# DE100-hw.net
KiCad netlist of a schematic drawn in EAGLE
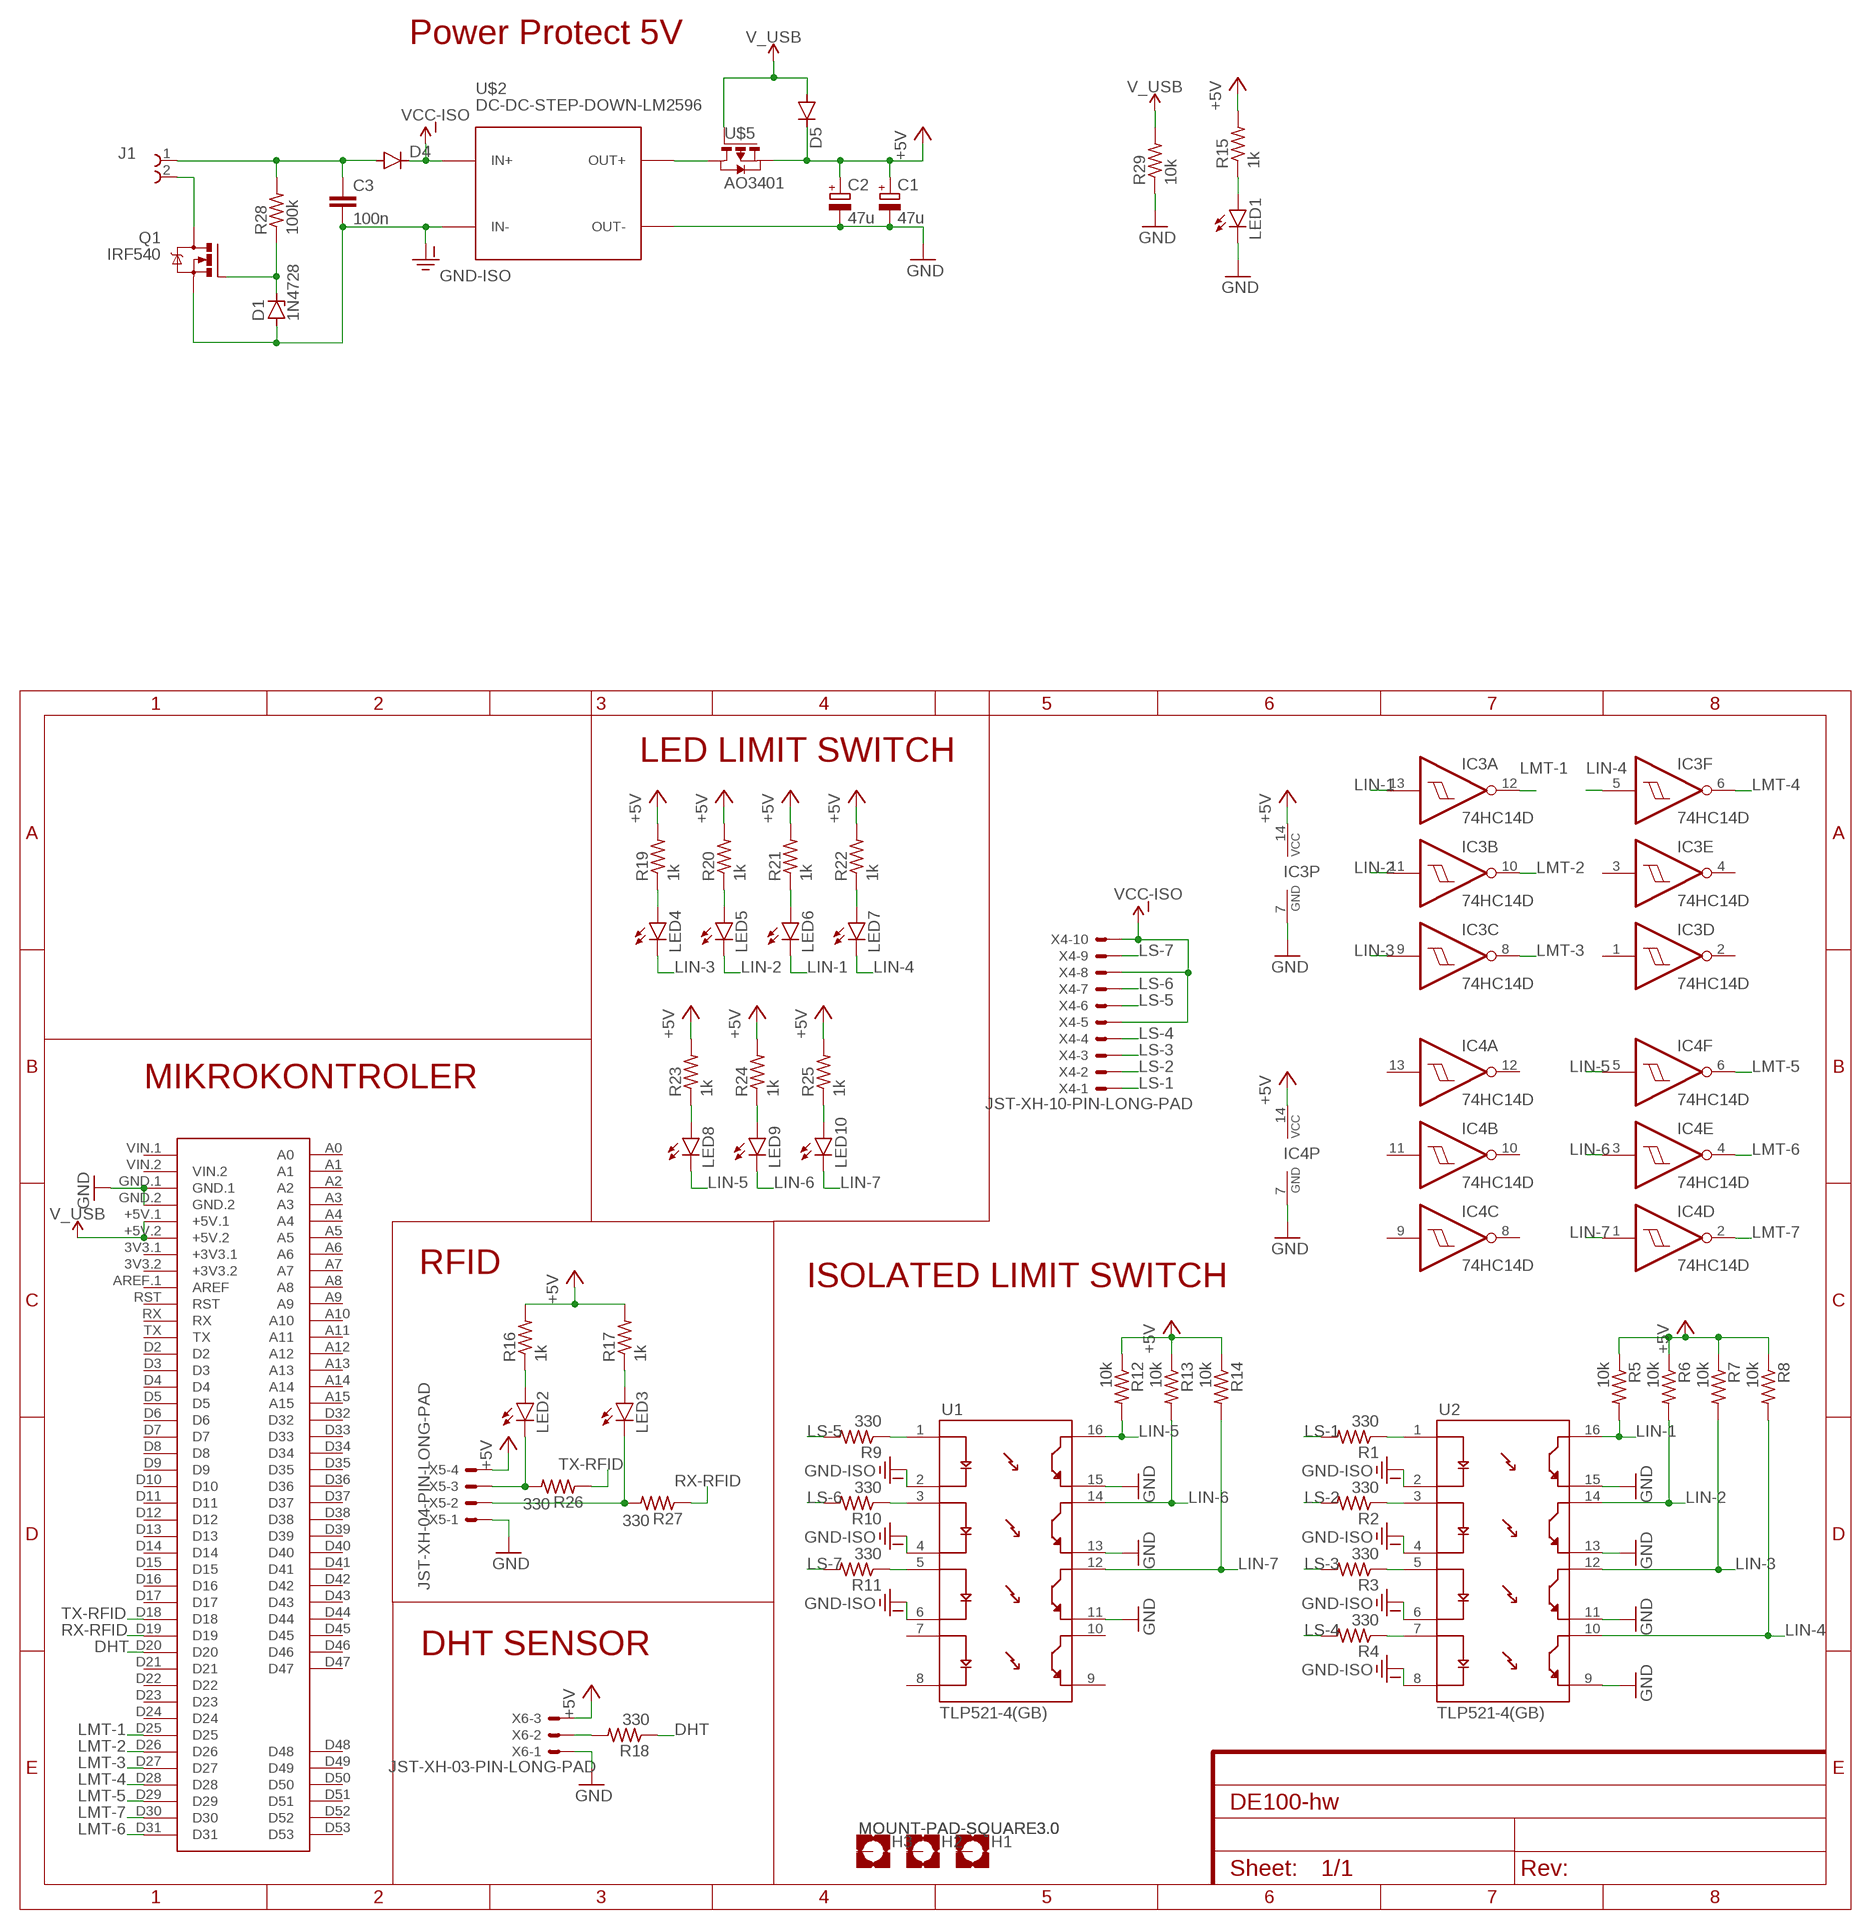
[diagram p0: schematic, sheet 1]

(export (version "E")
  (design (tool "Eeschema 10.0.6"))
  (components
    (comp (ref "C1")
      (value "47u")
      (footprint "eagle-import:UD-6,3X5,8_NICHICON")
      (libsource (lib "eagle-import") (part "CPOL-EUUD-6,3X8,8"))
    )
    (comp (ref "C2")
      (value "47u")
      (footprint "eagle-import:UD-6,3X5,8_NICHICON")
      (libsource (lib "eagle-import") (part "CPOL-EUUD-6,3X8,8"))
    )
    (comp (ref "C3")
      (value "100n")
      (footprint "eagle-import:C0805K")
      (libsource (lib "eagle-import") (part "C-EUC0805K"))
    )
    (comp (ref "D1")
      (value "1N4728")
      (footprint "eagle-import:DO41Z10")
      (libsource (lib "eagle-import") (part "1N4728"))
    )
    (comp (ref "D4")
      (value "DIODE-DO-214AC")
      (footprint "eagle-import:DO-214AC")
      (libsource (lib "eagle-import") (part "DIODE-DO-214AC"))
    )
    (comp (ref "D5")
      (value "DIODE-DO-214AC")
      (footprint "eagle-import:DO-214AC")
      (libsource (lib "eagle-import") (part "DIODE-DO-214AC"))
    )
    (comp (ref "H1")
      (value "MOUNT-PAD-SQUARE3.0")
      (footprint "eagle-import:3,0-PAD-SQUARE")
      (libsource (lib "eagle-import") (part "MOUNT-PAD-SQUARE3.0"))
    )
    (comp (ref "H2")
      (value "MOUNT-PAD-SQUARE3.0")
      (footprint "eagle-import:3,0-PAD-SQUARE")
      (libsource (lib "eagle-import") (part "MOUNT-PAD-SQUARE3.0"))
    )
    (comp (ref "H3")
      (value "MOUNT-PAD-SQUARE3.0")
      (footprint "eagle-import:3,0-PAD-SQUARE")
      (libsource (lib "eagle-import") (part "MOUNT-PAD-SQUARE3.0"))
    )
    (comp (ref "IC3")
      (value "74HC14D")
      (footprint "eagle-import:SO14")
      (libsource (lib "eagle-import") (part "7414DHC"))
    )
    (comp (ref "IC4")
      (value "74HC14D")
      (footprint "eagle-import:SO14")
      (libsource (lib "eagle-import") (part "7414DHC"))
    )
    (comp (ref "J1")
      (value "691312510002")
      (footprint "eagle-import:691312510002")
      (libsource (lib "eagle-import") (part "691312510002"))
    )
    (comp (ref "LED1")
      (value "LEDCHIPLED_0805")
      (footprint "eagle-import:CHIPLED_0805")
      (libsource (lib "eagle-import") (part "LEDCHIPLED_0805"))
    )
    (comp (ref "LED2")
      (value "LEDCHIPLED_0805")
      (footprint "eagle-import:CHIPLED_0805")
      (libsource (lib "eagle-import") (part "LEDCHIPLED_0805"))
    )
    (comp (ref "LED3")
      (value "LEDCHIPLED_0805")
      (footprint "eagle-import:CHIPLED_0805")
      (libsource (lib "eagle-import") (part "LEDCHIPLED_0805"))
    )
    (comp (ref "LED4")
      (value "LEDCHIPLED_0805")
      (footprint "eagle-import:CHIPLED_0805")
      (libsource (lib "eagle-import") (part "LEDCHIPLED_0805"))
    )
    (comp (ref "LED5")
      (value "LEDCHIPLED_0805")
      (footprint "eagle-import:CHIPLED_0805")
      (libsource (lib "eagle-import") (part "LEDCHIPLED_0805"))
    )
    (comp (ref "LED6")
      (value "LEDCHIPLED_0805")
      (footprint "eagle-import:CHIPLED_0805")
      (libsource (lib "eagle-import") (part "LEDCHIPLED_0805"))
    )
    (comp (ref "LED7")
      (value "LEDCHIPLED_0805")
      (footprint "eagle-import:CHIPLED_0805")
      (libsource (lib "eagle-import") (part "LEDCHIPLED_0805"))
    )
    (comp (ref "LED8")
      (value "LEDCHIPLED_0805")
      (footprint "eagle-import:CHIPLED_0805")
      (libsource (lib "eagle-import") (part "LEDCHIPLED_0805"))
    )
    (comp (ref "LED9")
      (value "LEDCHIPLED_0805")
      (footprint "eagle-import:CHIPLED_0805")
      (libsource (lib "eagle-import") (part "LEDCHIPLED_0805"))
    )
    (comp (ref "LED10")
      (value "LEDCHIPLED_0805")
      (footprint "eagle-import:CHIPLED_0805")
      (libsource (lib "eagle-import") (part "LEDCHIPLED_0805"))
    )
    (comp (ref "Q1")
      (value "IRF540")
      (footprint "eagle-import:TO220BV")
      (libsource (lib "eagle-import") (part "IRF540"))
    )
    (comp (ref "R1")
      (value "330")
      (footprint "eagle-import:R0805")
      (libsource (lib "eagle-import") (part "R-US_R0805"))
    )
    (comp (ref "R2")
      (value "330")
      (footprint "eagle-import:R0805")
      (libsource (lib "eagle-import") (part "R-US_R0805"))
    )
    (comp (ref "R3")
      (value "330")
      (footprint "eagle-import:R0805")
      (libsource (lib "eagle-import") (part "R-US_R0805"))
    )
    (comp (ref "R4")
      (value "330")
      (footprint "eagle-import:R0805")
      (libsource (lib "eagle-import") (part "R-US_R0805"))
    )
    (comp (ref "R5")
      (value "10k")
      (footprint "eagle-import:R0805")
      (libsource (lib "eagle-import") (part "R-US_R0805"))
    )
    (comp (ref "R6")
      (value "10k")
      (footprint "eagle-import:R0805")
      (libsource (lib "eagle-import") (part "R-US_R0805"))
    )
    (comp (ref "R7")
      (value "10k")
      (footprint "eagle-import:R0805")
      (libsource (lib "eagle-import") (part "R-US_R0805"))
    )
    (comp (ref "R8")
      (value "10k")
      (footprint "eagle-import:R0805")
      (libsource (lib "eagle-import") (part "R-US_R0805"))
    )
    (comp (ref "R9")
      (value "330")
      (footprint "eagle-import:R0805")
      (libsource (lib "eagle-import") (part "R-US_R0805"))
    )
    (comp (ref "R10")
      (value "330")
      (footprint "eagle-import:R0805")
      (libsource (lib "eagle-import") (part "R-US_R0805"))
    )
    (comp (ref "R11")
      (value "330")
      (footprint "eagle-import:R0805")
      (libsource (lib "eagle-import") (part "R-US_R0805"))
    )
    (comp (ref "R12")
      (value "10k")
      (footprint "eagle-import:R0805")
      (libsource (lib "eagle-import") (part "R-US_R0805"))
    )
    (comp (ref "R13")
      (value "10k")
      (footprint "eagle-import:R0805")
      (libsource (lib "eagle-import") (part "R-US_R0805"))
    )
    (comp (ref "R14")
      (value "10k")
      (footprint "eagle-import:R0805")
      (libsource (lib "eagle-import") (part "R-US_R0805"))
    )
    (comp (ref "R15")
      (value "1k")
      (footprint "eagle-import:R0805")
      (libsource (lib "eagle-import") (part "R-US_R0805"))
    )
    (comp (ref "R16")
      (value "1k")
      (footprint "eagle-import:R0805")
      (libsource (lib "eagle-import") (part "R-US_R0805"))
    )
    (comp (ref "R17")
      (value "1k")
      (footprint "eagle-import:R0805")
      (libsource (lib "eagle-import") (part "R-US_R0805"))
    )
    (comp (ref "R18")
      (value "330")
      (footprint "eagle-import:R0805")
      (libsource (lib "eagle-import") (part "R-US_R0805"))
    )
    (comp (ref "R19")
      (value "1k")
      (footprint "eagle-import:R0805")
      (libsource (lib "eagle-import") (part "R-US_R0805"))
    )
    (comp (ref "R20")
      (value "1k")
      (footprint "eagle-import:R0805")
      (libsource (lib "eagle-import") (part "R-US_R0805"))
    )
    (comp (ref "R21")
      (value "1k")
      (footprint "eagle-import:R0805")
      (libsource (lib "eagle-import") (part "R-US_R0805"))
    )
    (comp (ref "R22")
      (value "1k")
      (footprint "eagle-import:R0805")
      (libsource (lib "eagle-import") (part "R-US_R0805"))
    )
    (comp (ref "R23")
      (value "1k")
      (footprint "eagle-import:R0805")
      (libsource (lib "eagle-import") (part "R-US_R0805"))
    )
    (comp (ref "R24")
      (value "1k")
      (footprint "eagle-import:R0805")
      (libsource (lib "eagle-import") (part "R-US_R0805"))
    )
    (comp (ref "R25")
      (value "1k")
      (footprint "eagle-import:R0805")
      (libsource (lib "eagle-import") (part "R-US_R0805"))
    )
    (comp (ref "R26")
      (value "330")
      (footprint "eagle-import:R0805")
      (libsource (lib "eagle-import") (part "R-US_R0805"))
    )
    (comp (ref "R27")
      (value "330")
      (footprint "eagle-import:R0805")
      (libsource (lib "eagle-import") (part "R-US_R0805"))
    )
    (comp (ref "R28")
      (value "100k")
      (footprint "eagle-import:R0805")
      (libsource (lib "eagle-import") (part "R-US_R0805"))
    )
    (comp (ref "R29")
      (value "10k")
      (footprint "eagle-import:R0805")
      (libsource (lib "eagle-import") (part "R-US_R0805"))
    )
    (comp (ref "U$1")
      (value "MEGA2560_MIKRO")
      (footprint "eagle-import:MEGA2560_MIKRO")
      (libsource (lib "eagle-import") (part "MEGA2560_MIKRO"))
    )
    (comp (ref "U$2")
      (value "DC-DC-STEP-DOWN-LM2596")
      (footprint "eagle-import:DC-DC-STEP-DOWN-LM2596")
      (libsource (lib "eagle-import") (part "DC-DC-STEP-DOWN-LM2596"))
    )
    (comp (ref "U$5")
      (value "AO3401")
      (footprint "eagle-import:SOT23")
      (fields (field (name "MF") "Alpha & Omega Semiconductor"))
      (libsource (lib "eagle-import") (part "AO3401"))
    )
    (comp (ref "U1")
      (value "TLP521-4(GB)")
      (footprint "eagle-import:DIP762W50P254L2007H485Q16")
      (fields (field (name "MF") "Toshiba") (field (name "MP") "TLP521-4_GB_"))
      (libsource (lib "eagle-import") (part "TLP521-4(GB)"))
    )
    (comp (ref "U2")
      (value "TLP521-4(GB)")
      (footprint "eagle-import:DIP762W50P254L2007H485Q16")
      (fields (field (name "MF") "Toshiba") (field (name "MP") "TLP521-4_GB_"))
      (libsource (lib "eagle-import") (part "TLP521-4(GB)"))
    )
    (comp (ref "X4")
      (value "JST-XH-10-PIN-LONG-PAD")
      (footprint "eagle-import:JST-XH-10-PACKAGE-LONG-PAD")
      (libsource (lib "eagle-import") (part "JST-XH-10-PIN-LONG-PAD"))
    )
    (comp (ref "X5")
      (value "JST-XH-04-PIN-LONG-PAD")
      (footprint "eagle-import:JST-XH-04-PACKAGE-LONG-PAD")
      (libsource (lib "eagle-import") (part "JST-XH-04-PIN-LONG-PAD"))
    )
    (comp (ref "X6")
      (value "JST-XH-03-PIN-LONG-PAD")
      (footprint "eagle-import:JST-XH-03-PACKAGE-LONG-PAD")
      (libsource (lib "eagle-import") (part "JST-XH-03-PIN-LONG-PAD"))
    )
  )
  (nets
    (net (code "1") (name "+5V") (class "Default")
      (node (ref "C1") (pin "+") (pinfunction "+_+") (pintype "passive"))
      (node (ref "C2") (pin "+") (pinfunction "+_+") (pintype "passive"))
      (node (ref "D5") (pin "C") (pinfunction "C_C") (pintype "passive"))
      (node (ref "IC3") (pin "14") (pinfunction "VCC_14") (pintype "power_in"))
      (node (ref "IC4") (pin "14") (pinfunction "VCC_14") (pintype "power_in"))
      (node (ref "R12") (pin "1") (pinfunction "1_1") (pintype "passive"))
      (node (ref "R13") (pin "1") (pinfunction "1_1") (pintype "passive"))
      (node (ref "R14") (pin "1") (pinfunction "1_1") (pintype "passive"))
      (node (ref "R15") (pin "2") (pinfunction "2_2") (pintype "passive"))
      (node (ref "R16") (pin "2") (pinfunction "2_2") (pintype "passive"))
      (node (ref "R17") (pin "2") (pinfunction "2_2") (pintype "passive"))
      (node (ref "R19") (pin "2") (pinfunction "2_2") (pintype "passive"))
      (node (ref "R20") (pin "2") (pinfunction "2_2") (pintype "passive"))
      (node (ref "R21") (pin "2") (pinfunction "2_2") (pintype "passive"))
      (node (ref "R22") (pin "2") (pinfunction "2_2") (pintype "passive"))
      (node (ref "R23") (pin "2") (pinfunction "2_2") (pintype "passive"))
      (node (ref "R24") (pin "2") (pinfunction "2_2") (pintype "passive"))
      (node (ref "R25") (pin "2") (pinfunction "2_2") (pintype "passive"))
      (node (ref "R5") (pin "1") (pinfunction "1_1") (pintype "passive"))
      (node (ref "R6") (pin "1") (pinfunction "1_1") (pintype "passive"))
      (node (ref "R7") (pin "1") (pinfunction "1_1") (pintype "passive"))
      (node (ref "R8") (pin "1") (pinfunction "1_1") (pintype "passive"))
      (node (ref "U$5") (pin "2") (pinfunction "S_2") (pintype "passive"))
      (node (ref "X5") (pin "4") (pinfunction "S_4") (pintype "passive"))
      (node (ref "X6") (pin "3") (pinfunction "S_3") (pintype "passive"))
    )
    (net (code "2") (name "/DHT") (class "Default")
      (node (ref "R18") (pin "1") (pinfunction "1_1") (pintype "passive"))
      (node (ref "U$1") (pin "D20") (pinfunction "D20_D20") (pintype "bidirectional"))
    )
    (net (code "3") (name "/LIN-1") (class "Default")
      (node (ref "IC3") (pin "13") (pinfunction "I_13") (pintype "input"))
      (node (ref "LED6") (pin "C") (pinfunction "C_C") (pintype "passive"))
      (node (ref "R5") (pin "2") (pinfunction "2_2") (pintype "passive"))
      (node (ref "U2") (pin "16") (pinfunction "CT1_16") (pintype "passive"))
    )
    (net (code "4") (name "/LIN-2") (class "Default")
      (node (ref "IC3") (pin "11") (pinfunction "I_11") (pintype "input"))
      (node (ref "LED5") (pin "C") (pinfunction "C_C") (pintype "passive"))
      (node (ref "R6") (pin "2") (pinfunction "2_2") (pintype "passive"))
      (node (ref "U2") (pin "14") (pinfunction "CT2_14") (pintype "passive"))
    )
    (net (code "5") (name "/LIN-3") (class "Default")
      (node (ref "IC3") (pin "9") (pinfunction "I_9") (pintype "input"))
      (node (ref "LED4") (pin "C") (pinfunction "C_C") (pintype "passive"))
      (node (ref "R7") (pin "2") (pinfunction "2_2") (pintype "passive"))
      (node (ref "U2") (pin "12") (pinfunction "CT3_12") (pintype "passive"))
    )
    (net (code "6") (name "/LIN-4") (class "Default")
      (node (ref "IC3") (pin "5") (pinfunction "I_5") (pintype "input"))
      (node (ref "LED7") (pin "C") (pinfunction "C_C") (pintype "passive"))
      (node (ref "R8") (pin "2") (pinfunction "2_2") (pintype "passive"))
      (node (ref "U2") (pin "10") (pinfunction "CT4_10") (pintype "passive"))
    )
    (net (code "7") (name "/LIN-5") (class "Default")
      (node (ref "IC4") (pin "5") (pinfunction "I_5") (pintype "input"))
      (node (ref "LED8") (pin "C") (pinfunction "C_C") (pintype "passive"))
      (node (ref "R12") (pin "2") (pinfunction "2_2") (pintype "passive"))
      (node (ref "U1") (pin "16") (pinfunction "CT1_16") (pintype "passive"))
    )
    (net (code "8") (name "/LIN-6") (class "Default")
      (node (ref "IC4") (pin "3") (pinfunction "I_3") (pintype "input"))
      (node (ref "LED9") (pin "C") (pinfunction "C_C") (pintype "passive"))
      (node (ref "R13") (pin "2") (pinfunction "2_2") (pintype "passive"))
      (node (ref "U1") (pin "14") (pinfunction "CT2_14") (pintype "passive"))
    )
    (net (code "9") (name "/LIN-7") (class "Default")
      (node (ref "IC4") (pin "1") (pinfunction "I_1") (pintype "input"))
      (node (ref "LED10") (pin "C") (pinfunction "C_C") (pintype "passive"))
      (node (ref "R14") (pin "2") (pinfunction "2_2") (pintype "passive"))
      (node (ref "U1") (pin "12") (pinfunction "CT3_12") (pintype "passive"))
    )
    (net (code "10") (name "/LMT-1") (class "Default")
      (node (ref "IC3") (pin "12") (pinfunction "O_12") (pintype "output"))
      (node (ref "U$1") (pin "D25") (pinfunction "D25_D25") (pintype "bidirectional"))
    )
    (net (code "11") (name "/LMT-2") (class "Default")
      (node (ref "IC3") (pin "10") (pinfunction "O_10") (pintype "output"))
      (node (ref "U$1") (pin "D26") (pinfunction "D26_D26") (pintype "bidirectional"))
    )
    (net (code "12") (name "/LMT-3") (class "Default")
      (node (ref "IC3") (pin "8") (pinfunction "O_8") (pintype "output"))
      (node (ref "U$1") (pin "D27") (pinfunction "D27_D27") (pintype "bidirectional"))
    )
    (net (code "13") (name "/LMT-4") (class "Default")
      (node (ref "IC3") (pin "6") (pinfunction "O_6") (pintype "output"))
      (node (ref "U$1") (pin "D28") (pinfunction "D28_D28") (pintype "bidirectional"))
    )
    (net (code "14") (name "/LMT-5") (class "Default")
      (node (ref "IC4") (pin "6") (pinfunction "O_6") (pintype "output"))
      (node (ref "U$1") (pin "D29") (pinfunction "D29_D29") (pintype "bidirectional"))
    )
    (net (code "15") (name "/LMT-6") (class "Default")
      (node (ref "IC4") (pin "4") (pinfunction "O_4") (pintype "output"))
      (node (ref "U$1") (pin "D31") (pinfunction "D31_D31") (pintype "bidirectional"))
    )
    (net (code "16") (name "/LMT-7") (class "Default")
      (node (ref "IC4") (pin "2") (pinfunction "O_2") (pintype "output"))
      (node (ref "U$1") (pin "D30") (pinfunction "D30_D30") (pintype "bidirectional"))
    )
    (net (code "17") (name "/LS-1") (class "Default")
      (node (ref "R1") (pin "2") (pinfunction "2_2") (pintype "passive"))
      (node (ref "X4") (pin "1") (pinfunction "S_1") (pintype "passive"))
    )
    (net (code "18") (name "/LS-2") (class "Default")
      (node (ref "R2") (pin "2") (pinfunction "2_2") (pintype "passive"))
      (node (ref "X4") (pin "2") (pinfunction "S_2") (pintype "passive"))
    )
    (net (code "19") (name "/LS-3") (class "Default")
      (node (ref "R3") (pin "2") (pinfunction "2_2") (pintype "passive"))
      (node (ref "X4") (pin "3") (pinfunction "S_3") (pintype "passive"))
    )
    (net (code "20") (name "/LS-4") (class "Default")
      (node (ref "R4") (pin "2") (pinfunction "2_2") (pintype "passive"))
      (node (ref "X4") (pin "4") (pinfunction "S_4") (pintype "passive"))
    )
    (net (code "21") (name "/LS-5") (class "Default")
      (node (ref "R9") (pin "2") (pinfunction "2_2") (pintype "passive"))
      (node (ref "X4") (pin "6") (pinfunction "S_6") (pintype "passive"))
    )
    (net (code "22") (name "/LS-6") (class "Default")
      (node (ref "R10") (pin "2") (pinfunction "2_2") (pintype "passive"))
      (node (ref "X4") (pin "7") (pinfunction "S_7") (pintype "passive"))
    )
    (net (code "23") (name "/LS-7") (class "Default")
      (node (ref "R11") (pin "2") (pinfunction "2_2") (pintype "passive"))
      (node (ref "X4") (pin "9") (pinfunction "S_9") (pintype "passive"))
    )
    (net (code "24") (name "/RX-RFID") (class "Default")
      (node (ref "R27") (pin "1") (pinfunction "1_1") (pintype "passive"))
      (node (ref "U$1") (pin "D19") (pinfunction "D19_D19") (pintype "bidirectional"))
    )
    (net (code "25") (name "/TX-RFID") (class "Default")
      (node (ref "R26") (pin "1") (pinfunction "1_1") (pintype "passive"))
      (node (ref "U$1") (pin "D18") (pinfunction "D18_D18") (pintype "bidirectional"))
    )
    (net (code "26") (name "GND") (class "Default")
      (node (ref "C1") (pin "-") (pinfunction "-_-") (pintype "passive"))
      (node (ref "C2") (pin "-") (pinfunction "-_-") (pintype "passive"))
      (node (ref "IC3") (pin "7") (pinfunction "GND_7") (pintype "power_in"))
      (node (ref "IC4") (pin "7") (pinfunction "GND_7") (pintype "power_in"))
      (node (ref "LED1") (pin "C") (pinfunction "C_C") (pintype "passive"))
      (node (ref "R29") (pin "1") (pinfunction "1_1") (pintype "passive"))
      (node (ref "U$1") (pin "GND.1") (pinfunction "GND.1_GND.1") (pintype "bidirectional"))
      (node (ref "U$1") (pin "GND.2") (pinfunction "GND.2_GND.2") (pintype "bidirectional"))
      (node (ref "U$2") (pin "OUT-") (pinfunction "OUT-_OUT-") (pintype "bidirectional"))
      (node (ref "U1") (pin "11") (pinfunction "ET3_11") (pintype "passive"))
      (node (ref "U1") (pin "13") (pinfunction "ET2_13") (pintype "passive"))
      (node (ref "U1") (pin "15") (pinfunction "ET1_15") (pintype "passive"))
      (node (ref "U2") (pin "11") (pinfunction "ET3_11") (pintype "passive"))
      (node (ref "U2") (pin "13") (pinfunction "ET2_13") (pintype "passive"))
      (node (ref "U2") (pin "15") (pinfunction "ET1_15") (pintype "passive"))
      (node (ref "U2") (pin "9") (pinfunction "ET4_9") (pintype "passive"))
      (node (ref "X5") (pin "1") (pinfunction "S_1") (pintype "passive"))
      (node (ref "X6") (pin "1") (pinfunction "S_1") (pintype "passive"))
    )
    (net (code "27") (name "GND-ISO") (class "Default")
      (node (ref "C3") (pin "2") (pinfunction "2_2") (pintype "passive"))
      (node (ref "D1") (pin "A") (pinfunction "A_A") (pintype "passive"))
      (node (ref "Q1") (pin "S") (pinfunction "S_S") (pintype "passive"))
      (node (ref "U$2") (pin "IN-") (pinfunction "IN-_IN-") (pintype "bidirectional"))
      (node (ref "U1") (pin "2") (pinfunction "C1_2") (pintype "passive"))
      (node (ref "U1") (pin "4") (pinfunction "C2_4") (pintype "passive"))
      (node (ref "U1") (pin "6") (pinfunction "C3_6") (pintype "passive"))
      (node (ref "U2") (pin "2") (pinfunction "C1_2") (pintype "passive"))
      (node (ref "U2") (pin "4") (pinfunction "C2_4") (pintype "passive"))
      (node (ref "U2") (pin "6") (pinfunction "C3_6") (pintype "passive"))
      (node (ref "U2") (pin "8") (pinfunction "C4_8") (pintype "passive"))
    )
    (net (code "28") (name "Net-(C3-Pad1)") (class "Default")
      (node (ref "C3") (pin "1") (pinfunction "1_1") (pintype "passive"))
      (node (ref "D4") (pin "A") (pinfunction "A_A") (pintype "passive"))
      (node (ref "J1") (pin "1") (pinfunction "1_1") (pintype "passive"))
      (node (ref "R28") (pin "2") (pinfunction "2_2") (pintype "passive"))
    )
    (net (code "29") (name "Net-(D1-PadC)") (class "Default")
      (node (ref "D1") (pin "C") (pinfunction "C_C") (pintype "passive"))
      (node (ref "Q1") (pin "G") (pinfunction "G_G") (pintype "passive"))
      (node (ref "R28") (pin "1") (pinfunction "1_1") (pintype "passive"))
    )
    (net (code "30") (name "Net-(J1-Pad2)") (class "Default")
      (node (ref "J1") (pin "2") (pinfunction "2_2") (pintype "passive"))
      (node (ref "Q1") (pin "D") (pinfunction "D_D") (pintype "passive"))
    )
    (net (code "31") (name "Net-(LED1-PadA)") (class "Default")
      (node (ref "LED1") (pin "A") (pinfunction "A_A") (pintype "passive"))
      (node (ref "R15") (pin "1") (pinfunction "1_1") (pintype "passive"))
    )
    (net (code "32") (name "Net-(LED2-PadA)") (class "Default")
      (node (ref "LED2") (pin "A") (pinfunction "A_A") (pintype "passive"))
      (node (ref "R16") (pin "1") (pinfunction "1_1") (pintype "passive"))
    )
    (net (code "33") (name "Net-(LED3-PadA)") (class "Default")
      (node (ref "LED3") (pin "A") (pinfunction "A_A") (pintype "passive"))
      (node (ref "R17") (pin "1") (pinfunction "1_1") (pintype "passive"))
    )
    (net (code "34") (name "Net-(LED4-PadA)") (class "Default")
      (node (ref "LED4") (pin "A") (pinfunction "A_A") (pintype "passive"))
      (node (ref "R19") (pin "1") (pinfunction "1_1") (pintype "passive"))
    )
    (net (code "35") (name "Net-(LED5-PadA)") (class "Default")
      (node (ref "LED5") (pin "A") (pinfunction "A_A") (pintype "passive"))
      (node (ref "R20") (pin "1") (pinfunction "1_1") (pintype "passive"))
    )
    (net (code "36") (name "Net-(LED6-PadA)") (class "Default")
      (node (ref "LED6") (pin "A") (pinfunction "A_A") (pintype "passive"))
      (node (ref "R21") (pin "1") (pinfunction "1_1") (pintype "passive"))
    )
    (net (code "37") (name "Net-(LED7-PadA)") (class "Default")
      (node (ref "LED7") (pin "A") (pinfunction "A_A") (pintype "passive"))
      (node (ref "R22") (pin "1") (pinfunction "1_1") (pintype "passive"))
    )
    (net (code "38") (name "Net-(LED8-PadA)") (class "Default")
      (node (ref "LED8") (pin "A") (pinfunction "A_A") (pintype "passive"))
      (node (ref "R23") (pin "1") (pinfunction "1_1") (pintype "passive"))
    )
    (net (code "39") (name "Net-(LED9-PadA)") (class "Default")
      (node (ref "LED9") (pin "A") (pinfunction "A_A") (pintype "passive"))
      (node (ref "R24") (pin "1") (pinfunction "1_1") (pintype "passive"))
    )
    (net (code "40") (name "Net-(LED10-PadA)") (class "Default")
      (node (ref "LED10") (pin "A") (pinfunction "A_A") (pintype "passive"))
      (node (ref "R25") (pin "1") (pinfunction "1_1") (pintype "passive"))
    )
    (net (code "41") (name "Net-(U$5-D)") (class "Default")
      (node (ref "U$2") (pin "OUT+") (pinfunction "OUT+_OUT+") (pintype "bidirectional"))
      (node (ref "U$5") (pin "3") (pinfunction "D_3") (pintype "passive"))
    )
    (net (code "42") (name "Net-(U1-A1)") (class "Default")
      (node (ref "R9") (pin "1") (pinfunction "1_1") (pintype "passive"))
      (node (ref "U1") (pin "1") (pinfunction "A1_1") (pintype "passive"))
    )
    (net (code "43") (name "Net-(U1-A2)") (class "Default")
      (node (ref "R10") (pin "1") (pinfunction "1_1") (pintype "passive"))
      (node (ref "U1") (pin "3") (pinfunction "A2_3") (pintype "passive"))
    )
    (net (code "44") (name "Net-(U1-A3)") (class "Default")
      (node (ref "R11") (pin "1") (pinfunction "1_1") (pintype "passive"))
      (node (ref "U1") (pin "5") (pinfunction "A3_5") (pintype "passive"))
    )
    (net (code "45") (name "Net-(U2-A1)") (class "Default")
      (node (ref "R1") (pin "1") (pinfunction "1_1") (pintype "passive"))
      (node (ref "U2") (pin "1") (pinfunction "A1_1") (pintype "passive"))
    )
    (net (code "46") (name "Net-(U2-A2)") (class "Default")
      (node (ref "R2") (pin "1") (pinfunction "1_1") (pintype "passive"))
      (node (ref "U2") (pin "3") (pinfunction "A2_3") (pintype "passive"))
    )
    (net (code "47") (name "Net-(U2-A3)") (class "Default")
      (node (ref "R3") (pin "1") (pinfunction "1_1") (pintype "passive"))
      (node (ref "U2") (pin "5") (pinfunction "A3_5") (pintype "passive"))
    )
    (net (code "48") (name "Net-(U2-A4)") (class "Default")
      (node (ref "R4") (pin "1") (pinfunction "1_1") (pintype "passive"))
      (node (ref "U2") (pin "7") (pinfunction "A4_7") (pintype "passive"))
    )
    (net (code "49") (name "Net-(X5B-S)") (class "Default")
      (node (ref "LED3") (pin "C") (pinfunction "C_C") (pintype "passive"))
      (node (ref "R27") (pin "2") (pinfunction "2_2") (pintype "passive"))
      (node (ref "X5") (pin "2") (pinfunction "S_2") (pintype "passive"))
    )
    (net (code "50") (name "Net-(X5C-S)") (class "Default")
      (node (ref "LED2") (pin "C") (pinfunction "C_C") (pintype "passive"))
      (node (ref "R26") (pin "2") (pinfunction "2_2") (pintype "passive"))
      (node (ref "X5") (pin "3") (pinfunction "S_3") (pintype "passive"))
    )
    (net (code "51") (name "Net-(X6B-S)") (class "Default")
      (node (ref "R18") (pin "2") (pinfunction "2_2") (pintype "passive"))
      (node (ref "X6") (pin "2") (pinfunction "S_2") (pintype "passive"))
    )
    (net (code "52") (name "VCC-ISO") (class "Default")
      (node (ref "D4") (pin "C") (pinfunction "C_C") (pintype "passive"))
      (node (ref "U$2") (pin "IN+") (pinfunction "IN+_IN+") (pintype "bidirectional"))
      (node (ref "X4") (pin "10") (pinfunction "S_10") (pintype "passive"))
      (node (ref "X4") (pin "5") (pinfunction "S_5") (pintype "passive"))
      (node (ref "X4") (pin "8") (pinfunction "S_8") (pintype "passive"))
    )
    (net (code "53") (name "V_USB") (class "Default")
      (node (ref "D5") (pin "A") (pinfunction "A_A") (pintype "passive"))
      (node (ref "R29") (pin "2") (pinfunction "2_2") (pintype "passive"))
      (node (ref "U$1") (pin "+5V.1") (pinfunction "+5V.1_+5V.1") (pintype "bidirectional"))
      (node (ref "U$1") (pin "+5V.2") (pinfunction "+5V.2_+5V.2") (pintype "bidirectional"))
      (node (ref "U$5") (pin "1") (pinfunction "G_1") (pintype "passive"))
    )
    (net (code "54") (name "unconnected-(H1-MOUNT-PadB3,0)") (class "Default")
      (node (ref "H1") (pin "B3,0") (pinfunction "MOUNT_B3,0") (pintype "passive"))
    )
    (net (code "55") (name "unconnected-(H2-MOUNT-PadB3,0)") (class "Default")
      (node (ref "H2") (pin "B3,0") (pinfunction "MOUNT_B3,0") (pintype "passive"))
    )
    (net (code "56") (name "unconnected-(H3-MOUNT-PadB3,0)") (class "Default")
      (node (ref "H3") (pin "B3,0") (pinfunction "MOUNT_B3,0") (pintype "passive"))
    )
    (net (code "57") (name "unconnected-(IC3D-I-Pad1)") (class "Default")
      (node (ref "IC3") (pin "1") (pinfunction "I_1") (pintype "input"))
    )
    (net (code "58") (name "unconnected-(IC3D-O-Pad2)") (class "Default")
      (node (ref "IC3") (pin "2") (pinfunction "O_2") (pintype "output"))
    )
    (net (code "59") (name "unconnected-(IC3E-I-Pad3)") (class "Default")
      (node (ref "IC3") (pin "3") (pinfunction "I_3") (pintype "input"))
    )
    (net (code "60") (name "unconnected-(IC3E-O-Pad4)") (class "Default")
      (node (ref "IC3") (pin "4") (pinfunction "O_4") (pintype "output"))
    )
    (net (code "61") (name "unconnected-(IC4A-I-Pad13)") (class "Default")
      (node (ref "IC4") (pin "13") (pinfunction "I_13") (pintype "input"))
    )
    (net (code "62") (name "unconnected-(IC4A-O-Pad12)") (class "Default")
      (node (ref "IC4") (pin "12") (pinfunction "O_12") (pintype "output"))
    )
    (net (code "63") (name "unconnected-(IC4B-I-Pad11)") (class "Default")
      (node (ref "IC4") (pin "11") (pinfunction "I_11") (pintype "input"))
    )
    (net (code "64") (name "unconnected-(IC4B-O-Pad10)") (class "Default")
      (node (ref "IC4") (pin "10") (pinfunction "O_10") (pintype "output"))
    )
    (net (code "65") (name "unconnected-(IC4C-I-Pad9)") (class "Default")
      (node (ref "IC4") (pin "9") (pinfunction "I_9") (pintype "input"))
    )
    (net (code "66") (name "unconnected-(IC4C-O-Pad8)") (class "Default")
      (node (ref "IC4") (pin "8") (pinfunction "O_8") (pintype "output"))
    )
    (net (code "67") (name "unconnected-(U$1-+3V3.1-Pad3V3.1)") (class "Default")
      (node (ref "U$1") (pin "3V3.1") (pinfunction "+3V3.1_3V3.1") (pintype "bidirectional"))
    )
    (net (code "68") (name "unconnected-(U$1-+3V3.2-Pad3V3.2)") (class "Default")
      (node (ref "U$1") (pin "3V3.2") (pinfunction "+3V3.2_3V3.2") (pintype "bidirectional"))
    )
    (net (code "69") (name "unconnected-(U$1-AREF-PadAREF.1)") (class "Default")
      (node (ref "U$1") (pin "AREF.1") (pinfunction "AREF_AREF.1") (pintype "bidirectional"))
    )
    (net (code "70") (name "unconnected-(U$1-PadA0)") (class "Default")
      (node (ref "U$1") (pin "A0") (pinfunction "A0_A0") (pintype "bidirectional"))
    )
    (net (code "71") (name "unconnected-(U$1-PadA1)") (class "Default")
      (node (ref "U$1") (pin "A1") (pinfunction "A1_A1") (pintype "bidirectional"))
    )
    (net (code "72") (name "unconnected-(U$1-PadA2)") (class "Default")
      (node (ref "U$1") (pin "A2") (pinfunction "A2_A2") (pintype "bidirectional"))
    )
    (net (code "73") (name "unconnected-(U$1-PadA3)") (class "Default")
      (node (ref "U$1") (pin "A3") (pinfunction "A3_A3") (pintype "bidirectional"))
    )
    (net (code "74") (name "unconnected-(U$1-PadA4)") (class "Default")
      (node (ref "U$1") (pin "A4") (pinfunction "A4_A4") (pintype "bidirectional"))
    )
    (net (code "75") (name "unconnected-(U$1-PadA5)") (class "Default")
      (node (ref "U$1") (pin "A5") (pinfunction "A5_A5") (pintype "bidirectional"))
    )
    (net (code "76") (name "unconnected-(U$1-PadA6)") (class "Default")
      (node (ref "U$1") (pin "A6") (pinfunction "A6_A6") (pintype "bidirectional"))
    )
    (net (code "77") (name "unconnected-(U$1-PadA7)") (class "Default")
      (node (ref "U$1") (pin "A7") (pinfunction "A7_A7") (pintype "bidirectional"))
    )
    (net (code "78") (name "unconnected-(U$1-PadA8)") (class "Default")
      (node (ref "U$1") (pin "A8") (pinfunction "A8_A8") (pintype "bidirectional"))
    )
    (net (code "79") (name "unconnected-(U$1-PadA9)") (class "Default")
      (node (ref "U$1") (pin "A9") (pinfunction "A9_A9") (pintype "bidirectional"))
    )
    (net (code "80") (name "unconnected-(U$1-PadA10)") (class "Default")
      (node (ref "U$1") (pin "A10") (pinfunction "A10_A10") (pintype "bidirectional"))
    )
    (net (code "81") (name "unconnected-(U$1-PadA11)") (class "Default")
      (node (ref "U$1") (pin "A11") (pinfunction "A11_A11") (pintype "bidirectional"))
    )
    (net (code "82") (name "unconnected-(U$1-PadA12)") (class "Default")
      (node (ref "U$1") (pin "A12") (pinfunction "A12_A12") (pintype "bidirectional"))
    )
    (net (code "83") (name "unconnected-(U$1-PadA13)") (class "Default")
      (node (ref "U$1") (pin "A13") (pinfunction "A13_A13") (pintype "bidirectional"))
    )
    (net (code "84") (name "unconnected-(U$1-PadA14)") (class "Default")
      (node (ref "U$1") (pin "A14") (pinfunction "A14_A14") (pintype "bidirectional"))
    )
    (net (code "85") (name "unconnected-(U$1-PadA15)") (class "Default")
      (node (ref "U$1") (pin "A15") (pinfunction "A15_A15") (pintype "bidirectional"))
    )
    (net (code "86") (name "unconnected-(U$1-PadD2)") (class "Default")
      (node (ref "U$1") (pin "D2") (pinfunction "D2_D2") (pintype "bidirectional"))
    )
    (net (code "87") (name "unconnected-(U$1-PadD3)") (class "Default")
      (node (ref "U$1") (pin "D3") (pinfunction "D3_D3") (pintype "bidirectional"))
    )
    (net (code "88") (name "unconnected-(U$1-PadD4)") (class "Default")
      (node (ref "U$1") (pin "D4") (pinfunction "D4_D4") (pintype "bidirectional"))
    )
    (net (code "89") (name "unconnected-(U$1-PadD5)") (class "Default")
      (node (ref "U$1") (pin "D5") (pinfunction "D5_D5") (pintype "bidirectional"))
    )
    (net (code "90") (name "unconnected-(U$1-PadD6)") (class "Default")
      (node (ref "U$1") (pin "D6") (pinfunction "D6_D6") (pintype "bidirectional"))
    )
    (net (code "91") (name "unconnected-(U$1-PadD7)") (class "Default")
      (node (ref "U$1") (pin "D7") (pinfunction "D7_D7") (pintype "bidirectional"))
    )
    (net (code "92") (name "unconnected-(U$1-PadD8)") (class "Default")
      (node (ref "U$1") (pin "D8") (pinfunction "D8_D8") (pintype "bidirectional"))
    )
    (net (code "93") (name "unconnected-(U$1-PadD9)") (class "Default")
      (node (ref "U$1") (pin "D9") (pinfunction "D9_D9") (pintype "bidirectional"))
    )
    (net (code "94") (name "unconnected-(U$1-PadD10)") (class "Default")
      (node (ref "U$1") (pin "D10") (pinfunction "D10_D10") (pintype "bidirectional"))
    )
    (net (code "95") (name "unconnected-(U$1-PadD11)") (class "Default")
      (node (ref "U$1") (pin "D11") (pinfunction "D11_D11") (pintype "bidirectional"))
    )
    (net (code "96") (name "unconnected-(U$1-PadD12)") (class "Default")
      (node (ref "U$1") (pin "D12") (pinfunction "D12_D12") (pintype "bidirectional"))
    )
    (net (code "97") (name "unconnected-(U$1-PadD13)") (class "Default")
      (node (ref "U$1") (pin "D13") (pinfunction "D13_D13") (pintype "bidirectional"))
    )
    (net (code "98") (name "unconnected-(U$1-PadD14)") (class "Default")
      (node (ref "U$1") (pin "D14") (pinfunction "D14_D14") (pintype "bidirectional"))
    )
    (net (code "99") (name "unconnected-(U$1-PadD15)") (class "Default")
      (node (ref "U$1") (pin "D15") (pinfunction "D15_D15") (pintype "bidirectional"))
    )
    (net (code "100") (name "unconnected-(U$1-PadD16)") (class "Default")
      (node (ref "U$1") (pin "D16") (pinfunction "D16_D16") (pintype "bidirectional"))
    )
    (net (code "101") (name "unconnected-(U$1-PadD17)") (class "Default")
      (node (ref "U$1") (pin "D17") (pinfunction "D17_D17") (pintype "bidirectional"))
    )
    (net (code "102") (name "unconnected-(U$1-PadD21)") (class "Default")
      (node (ref "U$1") (pin "D21") (pinfunction "D21_D21") (pintype "bidirectional"))
    )
    (net (code "103") (name "unconnected-(U$1-PadD22)") (class "Default")
      (node (ref "U$1") (pin "D22") (pinfunction "D22_D22") (pintype "bidirectional"))
    )
    (net (code "104") (name "unconnected-(U$1-PadD23)") (class "Default")
      (node (ref "U$1") (pin "D23") (pinfunction "D23_D23") (pintype "bidirectional"))
    )
    (net (code "105") (name "unconnected-(U$1-PadD24)") (class "Default")
      (node (ref "U$1") (pin "D24") (pinfunction "D24_D24") (pintype "bidirectional"))
    )
    (net (code "106") (name "unconnected-(U$1-PadD32)") (class "Default")
      (node (ref "U$1") (pin "D32") (pinfunction "D32_D32") (pintype "bidirectional"))
    )
    (net (code "107") (name "unconnected-(U$1-PadD33)") (class "Default")
      (node (ref "U$1") (pin "D33") (pinfunction "D33_D33") (pintype "bidirectional"))
    )
    (net (code "108") (name "unconnected-(U$1-PadD34)") (class "Default")
      (node (ref "U$1") (pin "D34") (pinfunction "D34_D34") (pintype "bidirectional"))
    )
    (net (code "109") (name "unconnected-(U$1-PadD35)") (class "Default")
      (node (ref "U$1") (pin "D35") (pinfunction "D35_D35") (pintype "bidirectional"))
    )
    (net (code "110") (name "unconnected-(U$1-PadD36)") (class "Default")
      (node (ref "U$1") (pin "D36") (pinfunction "D36_D36") (pintype "bidirectional"))
    )
    (net (code "111") (name "unconnected-(U$1-PadD37)") (class "Default")
      (node (ref "U$1") (pin "D37") (pinfunction "D37_D37") (pintype "bidirectional"))
    )
    (net (code "112") (name "unconnected-(U$1-PadD38)") (class "Default")
      (node (ref "U$1") (pin "D38") (pinfunction "D38_D38") (pintype "bidirectional"))
    )
    (net (code "113") (name "unconnected-(U$1-PadD39)") (class "Default")
      (node (ref "U$1") (pin "D39") (pinfunction "D39_D39") (pintype "bidirectional"))
    )
    (net (code "114") (name "unconnected-(U$1-PadD40)") (class "Default")
      (node (ref "U$1") (pin "D40") (pinfunction "D40_D40") (pintype "bidirectional"))
    )
    (net (code "115") (name "unconnected-(U$1-PadD41)") (class "Default")
      (node (ref "U$1") (pin "D41") (pinfunction "D41_D41") (pintype "bidirectional"))
    )
    (net (code "116") (name "unconnected-(U$1-PadD42)") (class "Default")
      (node (ref "U$1") (pin "D42") (pinfunction "D42_D42") (pintype "bidirectional"))
    )
    (net (code "117") (name "unconnected-(U$1-PadD43)") (class "Default")
      (node (ref "U$1") (pin "D43") (pinfunction "D43_D43") (pintype "bidirectional"))
    )
    (net (code "118") (name "unconnected-(U$1-PadD44)") (class "Default")
      (node (ref "U$1") (pin "D44") (pinfunction "D44_D44") (pintype "bidirectional"))
    )
    (net (code "119") (name "unconnected-(U$1-PadD45)") (class "Default")
      (node (ref "U$1") (pin "D45") (pinfunction "D45_D45") (pintype "bidirectional"))
    )
    (net (code "120") (name "unconnected-(U$1-PadD46)") (class "Default")
      (node (ref "U$1") (pin "D46") (pinfunction "D46_D46") (pintype "bidirectional"))
    )
    (net (code "121") (name "unconnected-(U$1-PadD47)") (class "Default")
      (node (ref "U$1") (pin "D47") (pinfunction "D47_D47") (pintype "bidirectional"))
    )
    (net (code "122") (name "unconnected-(U$1-PadD48)") (class "Default")
      (node (ref "U$1") (pin "D48") (pinfunction "D48_D48") (pintype "bidirectional"))
    )
    (net (code "123") (name "unconnected-(U$1-PadD49)") (class "Default")
      (node (ref "U$1") (pin "D49") (pinfunction "D49_D49") (pintype "bidirectional"))
    )
    (net (code "124") (name "unconnected-(U$1-PadD50)") (class "Default")
      (node (ref "U$1") (pin "D50") (pinfunction "D50_D50") (pintype "bidirectional"))
    )
    (net (code "125") (name "unconnected-(U$1-PadD51)") (class "Default")
      (node (ref "U$1") (pin "D51") (pinfunction "D51_D51") (pintype "bidirectional"))
    )
    (net (code "126") (name "unconnected-(U$1-PadD52)") (class "Default")
      (node (ref "U$1") (pin "D52") (pinfunction "D52_D52") (pintype "bidirectional"))
    )
    (net (code "127") (name "unconnected-(U$1-PadD53)") (class "Default")
      (node (ref "U$1") (pin "D53") (pinfunction "D53_D53") (pintype "bidirectional"))
    )
    (net (code "128") (name "unconnected-(U$1-PadRST)") (class "Default")
      (node (ref "U$1") (pin "RST") (pinfunction "RST_RST") (pintype "bidirectional"))
    )
    (net (code "129") (name "unconnected-(U$1-PadRX)") (class "Default")
      (node (ref "U$1") (pin "RX") (pinfunction "RX_RX") (pintype "bidirectional"))
    )
    (net (code "130") (name "unconnected-(U$1-PadTX)") (class "Default")
      (node (ref "U$1") (pin "TX") (pinfunction "TX_TX") (pintype "bidirectional"))
    )
    (net (code "131") (name "unconnected-(U$1-PadVIN.1)") (class "Default")
      (node (ref "U$1") (pin "VIN.1") (pinfunction "VIN.1_VIN.1") (pintype "bidirectional"))
    )
    (net (code "132") (name "unconnected-(U$1-PadVIN.2)") (class "Default")
      (node (ref "U$1") (pin "VIN.2") (pinfunction "VIN.2_VIN.2") (pintype "bidirectional"))
    )
    (net (code "133") (name "unconnected-(U1-A4-Pad7)") (class "Default")
      (node (ref "U1") (pin "7") (pinfunction "A4_7") (pintype "passive"))
    )
    (net (code "134") (name "unconnected-(U1-C4-Pad8)") (class "Default")
      (node (ref "U1") (pin "8") (pinfunction "C4_8") (pintype "passive"))
    )
    (net (code "135") (name "unconnected-(U1-CT4-Pad10)") (class "Default")
      (node (ref "U1") (pin "10") (pinfunction "CT4_10") (pintype "passive"))
    )
    (net (code "136") (name "unconnected-(U1-ET4-Pad9)") (class "Default")
      (node (ref "U1") (pin "9") (pinfunction "ET4_9") (pintype "passive"))
    )
  )
)
